# shield.net
KiCad netlist of a schematic drawn in EAGLE
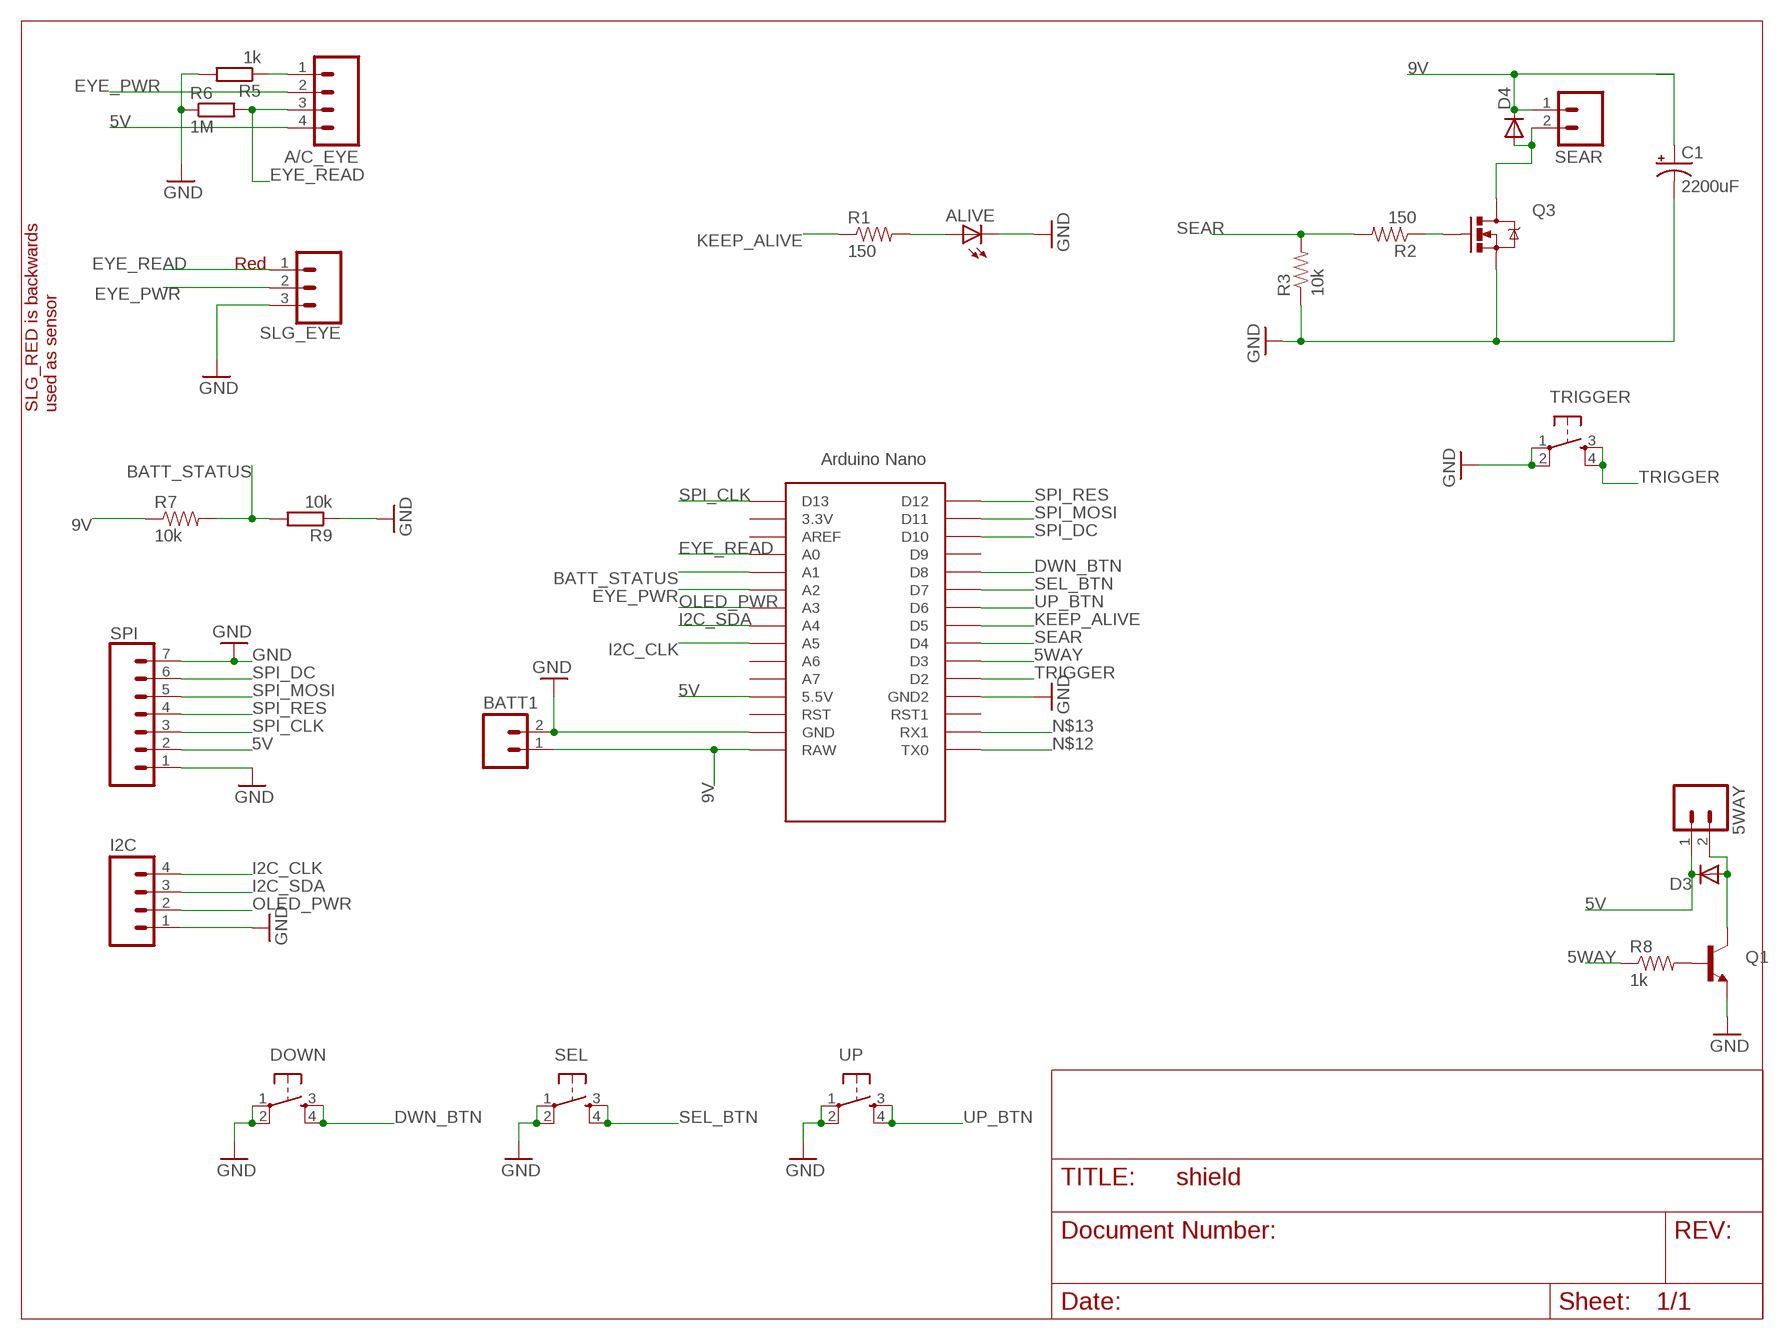
[diagram p0: schematic, sheet 1]

(export (version "E")
  (design (tool "Eeschema 10.0.6"))
  (components
    (comp (ref "5WAY")
      (value "M02PTH")
      (footprint "eagle-import:1X02")
      (libsource (lib "eagle-import") (part "M02PTH"))
    )
    (comp (ref "A/C_EYE")
      (value "M04PTH")
      (footprint "eagle-import:1X04")
      (libsource (lib "eagle-import") (part "M04PTH"))
    )
    (comp (ref "ALIVE")
      (value "LED3MM")
      (footprint "eagle-import:LED3MM")
      (libsource (lib "eagle-import") (part "LED3MM"))
    )
    (comp (ref "BATT1")
      (value "M02PTH")
      (footprint "eagle-import:1X02")
      (libsource (lib "eagle-import") (part "M02PTH"))
    )
    (comp (ref "C1")
      (value "2200uF")
      (footprint "eagle-import:CPOL-RADIAL-1000UF-25V")
      (libsource (lib "eagle-import") (part "CAP_POLPTH4"))
    )
    (comp (ref "D3")
      (value "DIODEPTH")
      (footprint "eagle-import:DIODE-1N4001")
      (libsource (lib "eagle-import") (part "DIODEPTH"))
    )
    (comp (ref "D4")
      (value "DIODEPTH")
      (footprint "eagle-import:DIODE-1N4001")
      (libsource (lib "eagle-import") (part "DIODEPTH"))
    )
    (comp (ref "DOWN")
      (value "TAC_SWITCHPTH")
      (footprint "eagle-import:TACTILE-PTH")
      (libsource (lib "eagle-import") (part "TAC_SWITCHPTH"))
    )
    (comp (ref "I2C")
      (value "M04PTH")
      (footprint "eagle-import:1X04")
      (libsource (lib "eagle-import") (part "M04PTH"))
    )
    (comp (ref "Q1")
      (value "TRANSISTOR_NPNTO-92-AMMO")
      (footprint "eagle-import:TO-92-AMMO")
      (libsource (lib "eagle-import") (part "TRANSISTOR_NPNTO-92-AMMO"))
    )
    (comp (ref "Q3")
      (value "MOSFET-NCHANNELPTH2")
      (footprint "eagle-import:TO220V")
      (libsource (lib "eagle-import") (part "MOSFET-NCHANNELPTH2"))
    )
    (comp (ref "R1")
      (value "150")
      (footprint "eagle-import:AXIAL-0.4")
      (libsource (lib "eagle-import") (part "RESISTORPTH-1/4W"))
    )
    (comp (ref "R2")
      (value "150")
      (footprint "eagle-import:AXIAL-0.4")
      (libsource (lib "eagle-import") (part "RESISTORPTH-1/4W"))
    )
    (comp (ref "R3")
      (value "10k")
      (footprint "eagle-import:AXIAL-0.4")
      (libsource (lib "eagle-import") (part "RESISTORPTH-1/4W"))
    )
    (comp (ref "R5")
      (value "1k")
      (footprint "eagle-import:0309V")
      (libsource (lib "eagle-import") (part "R-EU_0309/V"))
    )
    (comp (ref "R6")
      (value "1M")
      (footprint "eagle-import:0309V")
      (libsource (lib "eagle-import") (part "R-EU_0309/V"))
    )
    (comp (ref "R7")
      (value "10k")
      (footprint "eagle-import:AXIAL-0.4")
      (libsource (lib "eagle-import") (part "RESISTORPTH-1/4W"))
    )
    (comp (ref "R8")
      (value "1k")
      (footprint "eagle-import:AXIAL-0.4")
      (libsource (lib "eagle-import") (part "RESISTORPTH-1/4W"))
    )
    (comp (ref "R9")
      (value "10k")
      (footprint "eagle-import:0309V")
      (libsource (lib "eagle-import") (part "R-EU_0309/V"))
    )
    (comp (ref "SEAR")
      (value "M02PTH")
      (footprint "eagle-import:1X02")
      (libsource (lib "eagle-import") (part "M02PTH"))
    )
    (comp (ref "SEL")
      (value "TAC_SWITCHPTH")
      (footprint "eagle-import:TACTILE-PTH")
      (libsource (lib "eagle-import") (part "TAC_SWITCHPTH"))
    )
    (comp (ref "SLG_EYE")
      (value "CONN_03")
      (footprint "eagle-import:1X03")
      (libsource (lib "eagle-import") (part "CONN_03"))
    )
    (comp (ref "SPI")
      (value "CONN_07")
      (footprint "eagle-import:1X07")
      (libsource (lib "eagle-import") (part "CONN_07"))
    )
    (comp (ref "TRIGGER")
      (value "TAC_SWITCHPTH")
      (footprint "eagle-import:TACTILE-PTH")
      (libsource (lib "eagle-import") (part "TAC_SWITCHPTH"))
    )
    (comp (ref "U$5")
      (value "NANO")
      (footprint "eagle-import:NANO")
      (libsource (lib "eagle-import") (part "NANO"))
    )
    (comp (ref "UP")
      (value "TAC_SWITCHPTH")
      (footprint "eagle-import:TACTILE-PTH")
      (libsource (lib "eagle-import") (part "TAC_SWITCHPTH"))
    )
  )
  (nets
    (net (code "1") (name "/5V") (class "Default")
      (node (ref "5WAY") (pin "1") (pinfunction "1_1") (pintype "passive"))
      (node (ref "A/C_EYE") (pin "4") (pinfunction "4_4") (pintype "passive"))
      (node (ref "D3") (pin "C") (pinfunction "C_C") (pintype "passive"))
      (node (ref "SPI") (pin "2") (pinfunction "2_2") (pintype "passive"))
      (node (ref "U$5") (pin "5V") (pinfunction "5.5V_5V") (pintype "bidirectional"))
    )
    (net (code "2") (name "/5WAY") (class "Default")
      (node (ref "R8") (pin "P$1") (pinfunction "1_P$1") (pintype "passive"))
      (node (ref "U$5") (pin "D3") (pinfunction "D3_D3") (pintype "bidirectional"))
    )
    (net (code "3") (name "/9V") (class "Default")
      (node (ref "BATT1") (pin "1") (pinfunction "1_1") (pintype "passive"))
      (node (ref "C1") (pin "1") (pinfunction "+_1") (pintype "passive"))
      (node (ref "D4") (pin "C") (pinfunction "C_C") (pintype "passive"))
      (node (ref "R7") (pin "P$1") (pinfunction "1_P$1") (pintype "passive"))
      (node (ref "SEAR") (pin "1") (pinfunction "1_1") (pintype "passive"))
      (node (ref "U$5") (pin "RAW") (pinfunction "RAW_RAW") (pintype "bidirectional"))
    )
    (net (code "4") (name "/BATT_STATUS") (class "Default")
      (node (ref "R7") (pin "P$2") (pinfunction "2_P$2") (pintype "passive"))
      (node (ref "R9") (pin "2") (pinfunction "2_2") (pintype "passive"))
      (node (ref "U$5") (pin "A1") (pinfunction "A1_A1") (pintype "bidirectional"))
    )
    (net (code "5") (name "/DWN_BTN") (class "Default")
      (node (ref "DOWN") (pin "3") (pinfunction "3_3") (pintype "passive"))
      (node (ref "DOWN") (pin "4") (pinfunction "4_4") (pintype "passive"))
      (node (ref "U$5") (pin "D8") (pinfunction "D8_D8") (pintype "bidirectional"))
    )
    (net (code "6") (name "/EYE_PWR") (class "Default")
      (node (ref "A/C_EYE") (pin "2") (pinfunction "2_2") (pintype "passive"))
      (node (ref "SLG_EYE") (pin "2") (pinfunction "2_2") (pintype "passive"))
      (node (ref "U$5") (pin "A2") (pinfunction "A2_A2") (pintype "bidirectional"))
    )
    (net (code "7") (name "/EYE_READ") (class "Default")
      (node (ref "A/C_EYE") (pin "3") (pinfunction "3_3") (pintype "passive"))
      (node (ref "R6") (pin "2") (pinfunction "2_2") (pintype "passive"))
      (node (ref "SLG_EYE") (pin "1") (pinfunction "1_1") (pintype "passive"))
      (node (ref "U$5") (pin "A0") (pinfunction "A0_A0") (pintype "bidirectional"))
    )
    (net (code "8") (name "/I2C_CLK") (class "Default")
      (node (ref "I2C") (pin "4") (pinfunction "4_4") (pintype "passive"))
      (node (ref "U$5") (pin "A5") (pinfunction "A5_A5") (pintype "bidirectional"))
    )
    (net (code "9") (name "/I2C_SDA") (class "Default")
      (node (ref "I2C") (pin "3") (pinfunction "3_3") (pintype "passive"))
      (node (ref "U$5") (pin "A4") (pinfunction "A4_A4") (pintype "bidirectional"))
    )
    (net (code "10") (name "/KEEP_ALIVE") (class "Default")
      (node (ref "R1") (pin "P$1") (pinfunction "1_P$1") (pintype "passive"))
      (node (ref "U$5") (pin "D5") (pinfunction "D5_D5") (pintype "bidirectional"))
    )
    (net (code "11") (name "/N$12") (class "Default")
      (node (ref "U$5") (pin "TX0") (pinfunction "TX0_TX0") (pintype "bidirectional"))
    )
    (net (code "12") (name "/N$13") (class "Default")
      (node (ref "U$5") (pin "RX1") (pinfunction "RX1_RX1") (pintype "bidirectional"))
    )
    (net (code "13") (name "/OLED_PWR") (class "Default")
      (node (ref "I2C") (pin "2") (pinfunction "2_2") (pintype "passive"))
      (node (ref "U$5") (pin "A3") (pinfunction "A3_A3") (pintype "bidirectional"))
    )
    (net (code "14") (name "/SEAR") (class "Default")
      (node (ref "R2") (pin "P$2") (pinfunction "2_P$2") (pintype "passive"))
      (node (ref "R3") (pin "P$2") (pinfunction "2_P$2") (pintype "passive"))
      (node (ref "U$5") (pin "D4") (pinfunction "D4_D4") (pintype "bidirectional"))
    )
    (net (code "15") (name "/SEL_BTN") (class "Default")
      (node (ref "SEL") (pin "3") (pinfunction "3_3") (pintype "passive"))
      (node (ref "SEL") (pin "4") (pinfunction "4_4") (pintype "passive"))
      (node (ref "U$5") (pin "D7") (pinfunction "D7_D7") (pintype "bidirectional"))
    )
    (net (code "16") (name "/SPI_CLK") (class "Default")
      (node (ref "SPI") (pin "3") (pinfunction "3_3") (pintype "passive"))
      (node (ref "U$5") (pin "D13") (pinfunction "D13_D13") (pintype "bidirectional"))
    )
    (net (code "17") (name "/SPI_DC") (class "Default")
      (node (ref "SPI") (pin "6") (pinfunction "6_6") (pintype "passive"))
      (node (ref "U$5") (pin "D10") (pinfunction "D10_D10") (pintype "bidirectional"))
    )
    (net (code "18") (name "/SPI_MOSI") (class "Default")
      (node (ref "SPI") (pin "5") (pinfunction "5_5") (pintype "passive"))
      (node (ref "U$5") (pin "D11") (pinfunction "D11_D11") (pintype "bidirectional"))
    )
    (net (code "19") (name "/SPI_RES") (class "Default")
      (node (ref "SPI") (pin "4") (pinfunction "4_4") (pintype "passive"))
      (node (ref "U$5") (pin "D12") (pinfunction "D12_D12") (pintype "bidirectional"))
    )
    (net (code "20") (name "/TRIGGER") (class "Default")
      (node (ref "TRIGGER") (pin "3") (pinfunction "3_3") (pintype "passive"))
      (node (ref "TRIGGER") (pin "4") (pinfunction "4_4") (pintype "passive"))
      (node (ref "U$5") (pin "D2") (pinfunction "D2_D2") (pintype "bidirectional"))
    )
    (net (code "21") (name "/UP_BTN") (class "Default")
      (node (ref "U$5") (pin "D6") (pinfunction "D6_D6") (pintype "bidirectional"))
      (node (ref "UP") (pin "3") (pinfunction "3_3") (pintype "passive"))
      (node (ref "UP") (pin "4") (pinfunction "4_4") (pintype "passive"))
    )
    (net (code "22") (name "GND") (class "Default")
      (node (ref "ALIVE") (pin "K") (pinfunction "C_K") (pintype "passive"))
      (node (ref "BATT1") (pin "2") (pinfunction "2_2") (pintype "passive"))
      (node (ref "C1") (pin "2") (pinfunction "-_2") (pintype "passive"))
      (node (ref "DOWN") (pin "1") (pinfunction "1_1") (pintype "passive"))
      (node (ref "DOWN") (pin "2") (pinfunction "2_2") (pintype "passive"))
      (node (ref "I2C") (pin "1") (pinfunction "1_1") (pintype "passive"))
      (node (ref "Q1") (pin "1") (pinfunction "E_1") (pintype "passive"))
      (node (ref "Q3") (pin "3") (pinfunction "S_3") (pintype "passive"))
      (node (ref "R3") (pin "P$1") (pinfunction "1_P$1") (pintype "passive"))
      (node (ref "R5") (pin "2") (pinfunction "2_2") (pintype "passive"))
      (node (ref "R6") (pin "1") (pinfunction "1_1") (pintype "passive"))
      (node (ref "R9") (pin "1") (pinfunction "1_1") (pintype "passive"))
      (node (ref "SEL") (pin "1") (pinfunction "1_1") (pintype "passive"))
      (node (ref "SEL") (pin "2") (pinfunction "2_2") (pintype "passive"))
      (node (ref "SLG_EYE") (pin "3") (pinfunction "3_3") (pintype "passive"))
      (node (ref "SPI") (pin "1") (pinfunction "1_1") (pintype "passive"))
      (node (ref "SPI") (pin "7") (pinfunction "7_7") (pintype "passive"))
      (node (ref "TRIGGER") (pin "1") (pinfunction "1_1") (pintype "passive"))
      (node (ref "TRIGGER") (pin "2") (pinfunction "2_2") (pintype "passive"))
      (node (ref "U$5") (pin "GND") (pinfunction "GND_GND") (pintype "bidirectional"))
      (node (ref "U$5") (pin "GND1") (pinfunction "GND2_GND1") (pintype "bidirectional"))
      (node (ref "UP") (pin "1") (pinfunction "1_1") (pintype "passive"))
      (node (ref "UP") (pin "2") (pinfunction "2_2") (pintype "passive"))
    )
    (net (code "23") (name "Net-(A/C_EYE-Pad1)") (class "Default")
      (node (ref "A/C_EYE") (pin "1") (pinfunction "1_1") (pintype "passive"))
      (node (ref "R5") (pin "1") (pinfunction "1_1") (pintype "passive"))
    )
    (net (code "24") (name "Net-(Q1-B)") (class "Default")
      (node (ref "Q1") (pin "2") (pinfunction "B_2") (pintype "passive"))
      (node (ref "R8") (pin "P$2") (pinfunction "2_P$2") (pintype "passive"))
    )
    (net (code "25") (name "Net-(Q1-C)") (class "Default")
      (node (ref "5WAY") (pin "2") (pinfunction "2_2") (pintype "passive"))
      (node (ref "D3") (pin "A") (pinfunction "A_A") (pintype "passive"))
      (node (ref "Q1") (pin "3") (pinfunction "C_3") (pintype "passive"))
    )
    (net (code "26") (name "Net-(Q3-D)") (class "Default")
      (node (ref "D4") (pin "A") (pinfunction "A_A") (pintype "passive"))
      (node (ref "Q3") (pin "2") (pinfunction "D_2") (pintype "passive"))
      (node (ref "SEAR") (pin "2") (pinfunction "2_2") (pintype "passive"))
    )
    (net (code "27") (name "Net-(Q3-G)") (class "Default")
      (node (ref "Q3") (pin "1") (pinfunction "G_1") (pintype "passive"))
      (node (ref "R2") (pin "P$1") (pinfunction "1_P$1") (pintype "passive"))
    )
    (net (code "28") (name "Net-(R1-2)") (class "Default")
      (node (ref "ALIVE") (pin "A") (pinfunction "A_A") (pintype "passive"))
      (node (ref "R1") (pin "P$2") (pinfunction "2_P$2") (pintype "passive"))
    )
    (net (code "29") (name "unconnected-(U$5-Pad3.3V)") (class "Default")
      (node (ref "U$5") (pin "3.3V") (pinfunction "3.3V_3.3V") (pintype "bidirectional"))
    )
    (net (code "30") (name "unconnected-(U$5-PadA6)") (class "Default")
      (node (ref "U$5") (pin "A6") (pinfunction "A6_A6") (pintype "bidirectional"))
    )
    (net (code "31") (name "unconnected-(U$5-PadA7)") (class "Default")
      (node (ref "U$5") (pin "A7") (pinfunction "A7_A7") (pintype "bidirectional"))
    )
    (net (code "32") (name "unconnected-(U$5-PadAREF)") (class "Default")
      (node (ref "U$5") (pin "AREF") (pinfunction "AREF_AREF") (pintype "bidirectional"))
    )
    (net (code "33") (name "unconnected-(U$5-PadD9)") (class "Default")
      (node (ref "U$5") (pin "D9") (pinfunction "D9_D9") (pintype "bidirectional"))
    )
    (net (code "34") (name "unconnected-(U$5-PadICSP1)") (class "Default")
      (node (ref "U$5") (pin "ICSP1") (pinfunction "ICSP1_ICSP1") (pintype "bidirectional"))
    )
    (net (code "35") (name "unconnected-(U$5-PadICSP2)") (class "Default")
      (node (ref "U$5") (pin "ICSP2") (pinfunction "ICSP2_ICSP2") (pintype "bidirectional"))
    )
    (net (code "36") (name "unconnected-(U$5-PadICSP3)") (class "Default")
      (node (ref "U$5") (pin "ICSP3") (pinfunction "ICSP3_ICSP3") (pintype "bidirectional"))
    )
    (net (code "37") (name "unconnected-(U$5-PadICSP4)") (class "Default")
      (node (ref "U$5") (pin "ICSP4") (pinfunction "ICSP4_ICSP4") (pintype "bidirectional"))
    )
    (net (code "38") (name "unconnected-(U$5-PadICSP5)") (class "Default")
      (node (ref "U$5") (pin "ICSP5") (pinfunction "ICSP5_ICSP5") (pintype "bidirectional"))
    )
    (net (code "39") (name "unconnected-(U$5-PadICSP6)") (class "Default")
      (node (ref "U$5") (pin "ICSP6") (pinfunction "ICSP6_ICSP6") (pintype "bidirectional"))
    )
    (net (code "40") (name "unconnected-(U$5-PadRST)") (class "Default")
      (node (ref "U$5") (pin "RST") (pinfunction "RST_RST") (pintype "bidirectional"))
    )
    (net (code "41") (name "unconnected-(U$5-PadRST1)") (class "Default")
      (node (ref "U$5") (pin "RST1") (pinfunction "RST1_RST1") (pintype "bidirectional"))
    )
  )
)
